# esp-tom.net
KiCad netlist of a schematic drawn in EAGLE
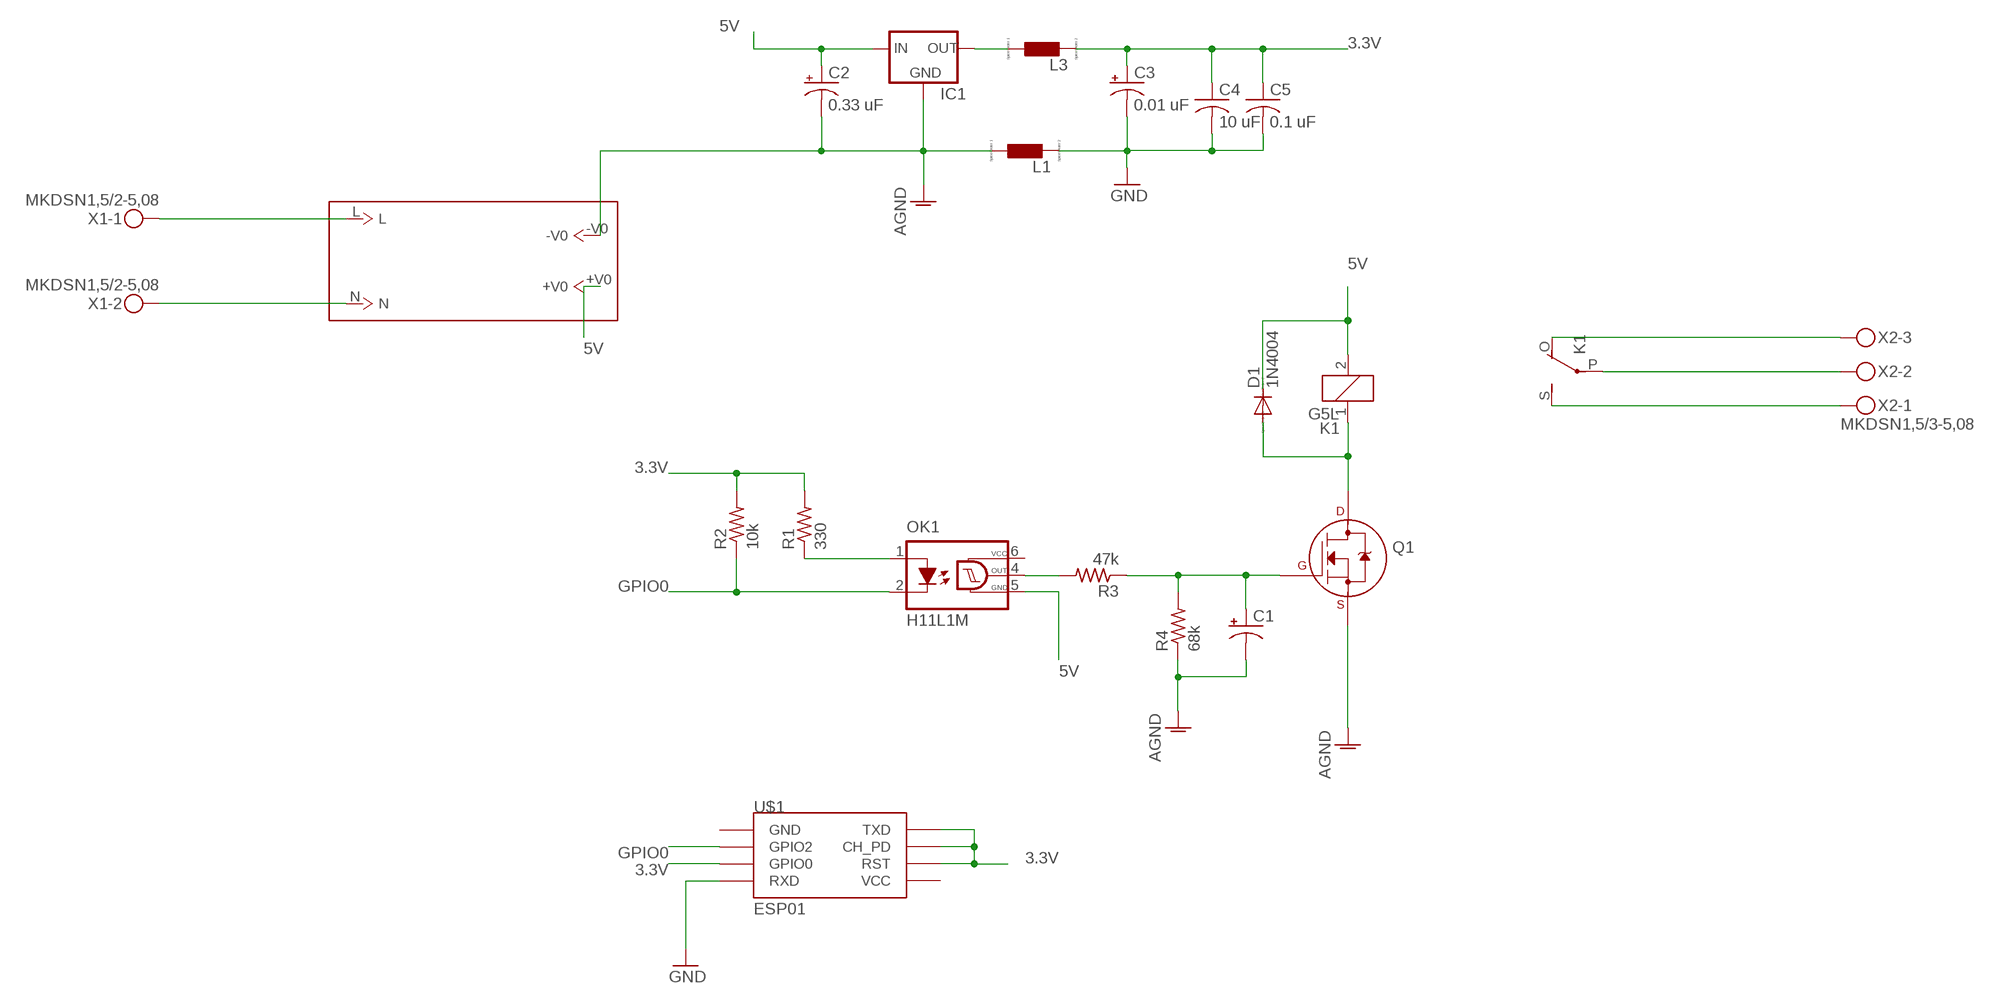
[diagram p0: schematic, sheet 1]

(export (version "E")
  (design (tool "Eeschema 10.0.6"))
  (components
    (comp (ref "C1")
      (value "CPOL-USE2-5")
      (footprint "eagle-import:E2-5")
      (libsource (lib "eagle-import") (part "CPOL-USE2-5"))
    )
    (comp (ref "C2")
      (value "0.33 uF")
      (footprint "eagle-import:E2-5")
      (libsource (lib "eagle-import") (part "CPOL-USE2-5"))
    )
    (comp (ref "C3")
      (value "0.01 uF")
      (footprint "eagle-import:E2-5")
      (libsource (lib "eagle-import") (part "CPOL-USE2-5"))
    )
    (comp (ref "C4")
      (value "10 uF")
      (footprint "eagle-import:C025-024X044")
      (libsource (lib "eagle-import") (part "C-US025-024X044"))
    )
    (comp (ref "C5")
      (value "0.1 uF")
      (footprint "eagle-import:C025-024X044")
      (libsource (lib "eagle-import") (part "C-US025-024X044"))
    )
    (comp (ref "D1")
      (value "1N4004")
      (footprint "eagle-import:DO41-10")
      (libsource (lib "eagle-import") (part "1N4004"))
    )
    (comp (ref "IC1")
      (value "78LXX")
      (footprint "eagle-import:78LXX")
      (libsource (lib "eagle-import") (part "78LXX"))
    )
    (comp (ref "K1")
      (value "G5L")
      (footprint "eagle-import:G5LE")
      (libsource (lib "eagle-import") (part "G5L"))
    )
    (comp (ref "L1")
      (value "L0207/10")
      (footprint "eagle-import:0207_10")
      (libsource (lib "eagle-import") (part "L0207/10"))
    )
    (comp (ref "L3")
      (value "L0207/10")
      (footprint "eagle-import:0207_10")
      (libsource (lib "eagle-import") (part "L0207/10"))
    )
    (comp (ref "OK1")
      (value "H11L1M")
      (footprint "eagle-import:DIL06")
      (fields (field (name "MF") "FAIRCHILD SEMICONDUCTOR") (field (name "MPN") "H11L1-M"))
      (libsource (lib "eagle-import") (part "H11LM1"))
    )
    (comp (ref "Q1")
      (value "2N7000_TO92")
      (footprint "eagle-import:TO-92")
      (libsource (lib "eagle-import") (part "2N700_TO920"))
    )
    (comp (ref "R1")
      (value "330")
      (footprint "eagle-import:0204_7")
      (libsource (lib "eagle-import") (part "R-US_0204/7"))
    )
    (comp (ref "R2")
      (value "10k")
      (footprint "eagle-import:0204_7")
      (libsource (lib "eagle-import") (part "R-US_0204/7"))
    )
    (comp (ref "R3")
      (value "47k")
      (footprint "eagle-import:0204_7")
      (libsource (lib "eagle-import") (part "R-US_0204/7"))
    )
    (comp (ref "R4")
      (value "68k")
      (footprint "eagle-import:0204_7")
      (libsource (lib "eagle-import") (part "R-US_0204/7"))
    )
    (comp (ref "U$1")
      (value "ESP01")
      (footprint "eagle-import:ESP01")
      (libsource (lib "eagle-import") (part "ESP01"))
    )
    (comp (ref "U$2")
      (value "NA03-T2S05")
      (footprint "eagle-import:NA03-T2S05")
      (libsource (lib "eagle-import") (part "NA03-T2S05"))
    )
    (comp (ref "X1")
      (value "MKDSN1,5/2-5,08")
      (footprint "eagle-import:MKDSN1,5_2-5,08")
      (libsource (lib "eagle-import") (part "MKDSN1,5/2-5,08"))
    )
    (comp (ref "X2")
      (value "MKDSN1,5/3-5,08")
      (footprint "eagle-import:MKDSN1,5_3-5,08")
      (libsource (lib "eagle-import") (part "MKDSN1,5/3-5,08"))
    )
  )
  (nets
    (net (code "1") (name "/3.3V") (class "Default")
      (node (ref "C3") (pin "+") (pinfunction "+_+") (pintype "passive"))
      (node (ref "C4") (pin "1") (pinfunction "1_1") (pintype "passive"))
      (node (ref "C5") (pin "1") (pinfunction "1_1") (pintype "passive"))
      (node (ref "L3") (pin "2") (pinfunction "2_2") (pintype "passive"))
      (node (ref "R1") (pin "2") (pinfunction "2_2") (pintype "passive"))
      (node (ref "R2") (pin "2") (pinfunction "2_2") (pintype "passive"))
      (node (ref "U$1") (pin "CH_PD") (pinfunction "CH_PD_CH_PD") (pintype "bidirectional"))
      (node (ref "U$1") (pin "GPIO0") (pinfunction "GPIO0_GPIO0") (pintype "bidirectional"))
      (node (ref "U$1") (pin "RST") (pinfunction "RST_RST") (pintype "bidirectional"))
      (node (ref "U$1") (pin "TX") (pinfunction "TXD_TX") (pintype "bidirectional"))
    )
    (net (code "2") (name "/5V") (class "Default")
      (node (ref "C2") (pin "+") (pinfunction "+_+") (pintype "passive"))
      (node (ref "D1") (pin "C") (pinfunction "C_C") (pintype "passive"))
      (node (ref "IC1") (pin "IN") (pinfunction "IN_IN") (pintype "input"))
      (node (ref "K1") (pin "2") (pinfunction "2_2") (pintype "passive"))
      (node (ref "OK1") (pin "5") (pinfunction "GND_5") (pintype "power_in"))
      (node (ref "U$2") (pin "+V0") (pinfunction "+V0_+V0") (pintype "bidirectional"))
    )
    (net (code "3") (name "/GPIO0") (class "Default")
      (node (ref "OK1") (pin "2") (pinfunction "C_2") (pintype "passive"))
      (node (ref "R2") (pin "1") (pinfunction "1_1") (pintype "passive"))
      (node (ref "U$1") (pin "GPIO2") (pinfunction "GPIO2_GPIO2") (pintype "bidirectional"))
    )
    (net (code "4") (name "/VCC") (class "Default")
      (node (ref "OK1") (pin "6") (pinfunction "VCC_6") (pintype "power_in"))
    )
    (net (code "5") (name "AGND") (class "Default")
      (node (ref "C1") (pin "-") (pinfunction "-_-") (pintype "passive"))
      (node (ref "C2") (pin "-") (pinfunction "-_-") (pintype "passive"))
      (node (ref "IC1") (pin "GND") (pinfunction "GND_GND") (pintype "input"))
      (node (ref "L1") (pin "1") (pinfunction "1_1") (pintype "passive"))
      (node (ref "Q1") (pin "1") (pinfunction "S_1") (pintype "bidirectional"))
      (node (ref "R4") (pin "1") (pinfunction "1_1") (pintype "passive"))
      (node (ref "U$2") (pin "-V0") (pinfunction "-V0_-V0") (pintype "bidirectional"))
    )
    (net (code "6") (name "GND") (class "Default")
      (node (ref "C3") (pin "-") (pinfunction "-_-") (pintype "passive"))
      (node (ref "C4") (pin "2") (pinfunction "2_2") (pintype "passive"))
      (node (ref "C5") (pin "2") (pinfunction "2_2") (pintype "passive"))
      (node (ref "L1") (pin "2") (pinfunction "2_2") (pintype "passive"))
      (node (ref "U$1") (pin "RX") (pinfunction "RXD_RX") (pintype "bidirectional"))
    )
    (net (code "7") (name "Net-(IC1-PadOUT)") (class "Default")
      (node (ref "IC1") (pin "OUT") (pinfunction "OUT_OUT") (pintype "passive"))
      (node (ref "L3") (pin "1") (pinfunction "1_1") (pintype "passive"))
    )
    (net (code "8") (name "Net-(OK1-A)") (class "Default")
      (node (ref "OK1") (pin "1") (pinfunction "A_1") (pintype "passive"))
      (node (ref "R1") (pin "1") (pinfunction "1_1") (pintype "passive"))
    )
    (net (code "9") (name "Net-(OK1-OUT)") (class "Default")
      (node (ref "OK1") (pin "4") (pinfunction "OUT_4") (pintype "output"))
      (node (ref "R3") (pin "2") (pinfunction "2_2") (pintype "passive"))
    )
    (net (code "10") (name "Net-(Q1-D)") (class "Default")
      (node (ref "D1") (pin "A") (pinfunction "A_A") (pintype "passive"))
      (node (ref "K1") (pin "1") (pinfunction "1_1") (pintype "passive"))
      (node (ref "Q1") (pin "3") (pinfunction "D_3") (pintype "bidirectional"))
    )
    (net (code "11") (name "Net-(Q1-G)") (class "Default")
      (node (ref "C1") (pin "+") (pinfunction "+_+") (pintype "passive"))
      (node (ref "Q1") (pin "2") (pinfunction "G_2") (pintype "tri_state"))
      (node (ref "R3") (pin "1") (pinfunction "1_1") (pintype "passive"))
      (node (ref "R4") (pin "2") (pinfunction "2_2") (pintype "passive"))
    )
    (net (code "12") (name "Net-(X1A-KL)") (class "Default")
      (node (ref "U$2") (pin "L") (pinfunction "L_L") (pintype "bidirectional"))
      (node (ref "X1") (pin "1") (pinfunction "KL_1") (pintype "passive"))
    )
    (net (code "13") (name "Net-(X1B-KL)") (class "Default")
      (node (ref "U$2") (pin "N") (pinfunction "N_N") (pintype "bidirectional"))
      (node (ref "X1") (pin "2") (pinfunction "KL_2") (pintype "passive"))
    )
    (net (code "14") (name "Net-(X2A-KL)") (class "Default")
      (node (ref "K1") (pin "S") (pinfunction "S_S") (pintype "passive"))
      (node (ref "X2") (pin "1") (pinfunction "KL_1") (pintype "passive"))
    )
    (net (code "15") (name "Net-(X2B-KL)") (class "Default")
      (node (ref "K1") (pin "P") (pinfunction "P_P") (pintype "passive"))
      (node (ref "X2") (pin "2") (pinfunction "KL_2") (pintype "passive"))
    )
    (net (code "16") (name "Net-(X2C-KL)") (class "Default")
      (node (ref "K1") (pin "O") (pinfunction "O_O") (pintype "passive"))
      (node (ref "X2") (pin "3") (pinfunction "KL_3") (pintype "passive"))
    )
    (net (code "17") (name "unconnected-(U$1-PadGND)") (class "Default")
      (node (ref "U$1") (pin "GND") (pinfunction "GND_GND") (pintype "bidirectional"))
    )
    (net (code "18") (name "unconnected-(U$1-PadVCC)") (class "Default")
      (node (ref "U$1") (pin "VCC") (pinfunction "VCC_VCC") (pintype "bidirectional"))
    )
  )
)
